# TinyCube13_FourLayer.net
KiCad netlist of a schematic drawn in EAGLE
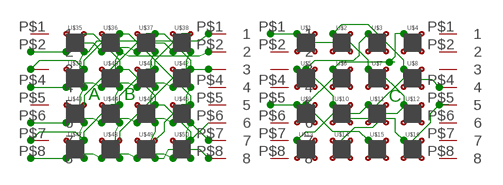
[diagram p0: schematic, sheet 1]

(export (version "E")
  (design (tool "Eeschema 10.0.6"))
  (components
    (comp (ref "JP1")
      (value "TINY_HEADER_DEV")
      (footprint "eagle-import:TINY_HEADER_PKG")
      (libsource (lib "eagle-import") (part "TINY_HEADER_DEV"))
    )
    (comp (ref "JP2")
      (value "TINY_HEADER_DEV")
      (footprint "eagle-import:TINY_HEADER_PKG")
      (libsource (lib "eagle-import") (part "TINY_HEADER_DEV"))
    )
    (comp (ref "U$1")
      (value "PILLAR")
      (footprint "eagle-import:10MIL")
      (libsource (lib "eagle-import") (part "PILLAR"))
    )
    (comp (ref "U$2")
      (value "PILLAR")
      (footprint "eagle-import:10MIL")
      (libsource (lib "eagle-import") (part "PILLAR"))
    )
    (comp (ref "U$3")
      (value "PILLAR")
      (footprint "eagle-import:10MIL")
      (libsource (lib "eagle-import") (part "PILLAR"))
    )
    (comp (ref "U$4")
      (value "PILLAR")
      (footprint "eagle-import:10MIL")
      (libsource (lib "eagle-import") (part "PILLAR"))
    )
    (comp (ref "U$5")
      (value "PILLAR")
      (footprint "eagle-import:10MIL")
      (libsource (lib "eagle-import") (part "PILLAR"))
    )
    (comp (ref "U$6")
      (value "PILLAR")
      (footprint "eagle-import:10MIL")
      (libsource (lib "eagle-import") (part "PILLAR"))
    )
    (comp (ref "U$7")
      (value "PILLAR")
      (footprint "eagle-import:10MIL")
      (libsource (lib "eagle-import") (part "PILLAR"))
    )
    (comp (ref "U$8")
      (value "PILLAR")
      (footprint "eagle-import:10MIL")
      (libsource (lib "eagle-import") (part "PILLAR"))
    )
    (comp (ref "U$9")
      (value "PILLAR")
      (footprint "eagle-import:10MIL")
      (libsource (lib "eagle-import") (part "PILLAR"))
    )
    (comp (ref "U$10")
      (value "PILLAR")
      (footprint "eagle-import:10MIL")
      (libsource (lib "eagle-import") (part "PILLAR"))
    )
    (comp (ref "U$11")
      (value "PILLAR")
      (footprint "eagle-import:10MIL")
      (libsource (lib "eagle-import") (part "PILLAR"))
    )
    (comp (ref "U$12")
      (value "PILLAR")
      (footprint "eagle-import:10MIL")
      (libsource (lib "eagle-import") (part "PILLAR"))
    )
    (comp (ref "U$13")
      (value "PILLAR")
      (footprint "eagle-import:10MIL")
      (libsource (lib "eagle-import") (part "PILLAR"))
    )
    (comp (ref "U$14")
      (value "PILLAR")
      (footprint "eagle-import:10MIL")
      (libsource (lib "eagle-import") (part "PILLAR"))
    )
    (comp (ref "U$15")
      (value "PILLAR")
      (footprint "eagle-import:10MIL")
      (libsource (lib "eagle-import") (part "PILLAR"))
    )
    (comp (ref "U$16")
      (value "PILLAR")
      (footprint "eagle-import:10MIL")
      (libsource (lib "eagle-import") (part "PILLAR"))
    )
    (comp (ref "U$35")
      (value "PILLAR")
      (footprint "eagle-import:10MIL")
      (libsource (lib "eagle-import") (part "PILLAR"))
    )
    (comp (ref "U$36")
      (value "PILLAR")
      (footprint "eagle-import:10MIL")
      (libsource (lib "eagle-import") (part "PILLAR"))
    )
    (comp (ref "U$37")
      (value "PILLAR")
      (footprint "eagle-import:10MIL")
      (libsource (lib "eagle-import") (part "PILLAR"))
    )
    (comp (ref "U$38")
      (value "PILLAR")
      (footprint "eagle-import:10MIL")
      (libsource (lib "eagle-import") (part "PILLAR"))
    )
    (comp (ref "U$39")
      (value "PILLAR")
      (footprint "eagle-import:10MIL")
      (libsource (lib "eagle-import") (part "PILLAR"))
    )
    (comp (ref "U$40")
      (value "PILLAR")
      (footprint "eagle-import:10MIL")
      (libsource (lib "eagle-import") (part "PILLAR"))
    )
    (comp (ref "U$41")
      (value "PILLAR")
      (footprint "eagle-import:10MIL")
      (libsource (lib "eagle-import") (part "PILLAR"))
    )
    (comp (ref "U$42")
      (value "PILLAR")
      (footprint "eagle-import:10MIL")
      (libsource (lib "eagle-import") (part "PILLAR"))
    )
    (comp (ref "U$43")
      (value "PILLAR")
      (footprint "eagle-import:10MIL")
      (libsource (lib "eagle-import") (part "PILLAR"))
    )
    (comp (ref "U$44")
      (value "PILLAR")
      (footprint "eagle-import:10MIL")
      (libsource (lib "eagle-import") (part "PILLAR"))
    )
    (comp (ref "U$45")
      (value "PILLAR")
      (footprint "eagle-import:10MIL")
      (libsource (lib "eagle-import") (part "PILLAR"))
    )
    (comp (ref "U$46")
      (value "PILLAR")
      (footprint "eagle-import:10MIL")
      (libsource (lib "eagle-import") (part "PILLAR"))
    )
    (comp (ref "U$47")
      (value "PILLAR")
      (footprint "eagle-import:10MIL")
      (libsource (lib "eagle-import") (part "PILLAR"))
    )
    (comp (ref "U$48")
      (value "PILLAR")
      (footprint "eagle-import:10MIL")
      (libsource (lib "eagle-import") (part "PILLAR"))
    )
    (comp (ref "U$49")
      (value "PILLAR")
      (footprint "eagle-import:10MIL")
      (libsource (lib "eagle-import") (part "PILLAR"))
    )
    (comp (ref "U$50")
      (value "PILLAR")
      (footprint "eagle-import:10MIL")
      (libsource (lib "eagle-import") (part "PILLAR"))
    )
    (comp (ref "U$51")
      (value "TINY_HEADER_DEV")
      (footprint "eagle-import:TINY_HEADER_PKG")
      (libsource (lib "eagle-import") (part "TINY_HEADER_DEV"))
    )
    (comp (ref "U$52")
      (value "TINY_HEADER_DEV")
      (footprint "eagle-import:TINY_HEADER_PKG")
      (libsource (lib "eagle-import") (part "TINY_HEADER_DEV"))
    )
  )
  (nets
    (net (code "1") (name "Net-(JP1-1)") (class "Default")
      (node (ref "JP1") (pin "P$1") (pinfunction "1_P$1") (pintype "input"))
      (node (ref "U$1") (pin "R") (pinfunction "B_R") (pintype "bidirectional"))
      (node (ref "U$12") (pin "R") (pinfunction "B_R") (pintype "bidirectional"))
      (node (ref "U$14") (pin "R") (pinfunction "B_R") (pintype "bidirectional"))
      (node (ref "U$7") (pin "R") (pinfunction "B_R") (pintype "bidirectional"))
    )
    (net (code "2") (name "Net-(JP1-5)") (class "Default")
      (node (ref "JP1") (pin "P$5") (pinfunction "5_P$5") (pintype "bidirectional"))
      (node (ref "U$15") (pin "R") (pinfunction "B_R") (pintype "bidirectional"))
      (node (ref "U$4") (pin "R") (pinfunction "B_R") (pintype "bidirectional"))
      (node (ref "U$6") (pin "R") (pinfunction "B_R") (pintype "bidirectional"))
      (node (ref "U$9") (pin "R") (pinfunction "B_R") (pintype "bidirectional"))
    )
    (net (code "3") (name "Net-(JP2-4)") (class "Default")
      (node (ref "JP2") (pin "P$4") (pinfunction "4_P$4") (pintype "bidirectional"))
      (node (ref "U$11") (pin "R") (pinfunction "B_R") (pintype "bidirectional"))
      (node (ref "U$13") (pin "R") (pinfunction "B_R") (pintype "bidirectional"))
      (node (ref "U$2") (pin "R") (pinfunction "B_R") (pintype "bidirectional"))
      (node (ref "U$8") (pin "R") (pinfunction "B_R") (pintype "bidirectional"))
    )
    (net (code "4") (name "Net-(JP2-5)") (class "Default")
      (node (ref "JP2") (pin "P$5") (pinfunction "5_P$5") (pintype "bidirectional"))
      (node (ref "U$10") (pin "R") (pinfunction "B_R") (pintype "bidirectional"))
      (node (ref "U$16") (pin "R") (pinfunction "B_R") (pintype "bidirectional"))
      (node (ref "U$3") (pin "R") (pinfunction "B_R") (pintype "bidirectional"))
      (node (ref "U$5") (pin "R") (pinfunction "B_R") (pintype "bidirectional"))
    )
    (net (code "5") (name "Net-(U$35-A)") (class "Default")
      (node (ref "U$35") (pin "G") (pinfunction "A_G") (pintype "bidirectional"))
      (node (ref "U$36") (pin "G") (pinfunction "A_G") (pintype "bidirectional"))
      (node (ref "U$37") (pin "G") (pinfunction "A_G") (pintype "bidirectional"))
      (node (ref "U$38") (pin "G") (pinfunction "A_G") (pintype "bidirectional"))
      (node (ref "U$51") (pin "P$2") (pinfunction "2_P$2") (pintype "bidirectional"))
    )
    (net (code "6") (name "Net-(U$35-G)") (class "Default")
      (node (ref "U$35") (pin "+") (pinfunction "G_+") (pintype "bidirectional"))
      (node (ref "U$40") (pin "+") (pinfunction "G_+") (pintype "bidirectional"))
      (node (ref "U$45") (pin "+") (pinfunction "G_+") (pintype "bidirectional"))
      (node (ref "U$50") (pin "+") (pinfunction "G_+") (pintype "bidirectional"))
      (node (ref "U$52") (pin "P$6") (pinfunction "6_P$6") (pintype "bidirectional"))
    )
    (net (code "7") (name "Net-(U$35-R)") (class "Default")
      (node (ref "U$35") (pin "B") (pinfunction "R_B") (pintype "bidirectional"))
      (node (ref "U$39") (pin "B") (pinfunction "R_B") (pintype "bidirectional"))
      (node (ref "U$43") (pin "B") (pinfunction "R_B") (pintype "bidirectional"))
      (node (ref "U$47") (pin "B") (pinfunction "R_B") (pintype "bidirectional"))
      (node (ref "U$52") (pin "P$1") (pinfunction "1_P$1") (pintype "input"))
    )
    (net (code "8") (name "Net-(U$36-G)") (class "Default")
      (node (ref "U$36") (pin "+") (pinfunction "G_+") (pintype "bidirectional"))
      (node (ref "U$39") (pin "+") (pinfunction "G_+") (pintype "bidirectional"))
      (node (ref "U$46") (pin "+") (pinfunction "G_+") (pintype "bidirectional"))
      (node (ref "U$49") (pin "+") (pinfunction "G_+") (pintype "bidirectional"))
      (node (ref "U$51") (pin "P$3") (pinfunction "3_P$3") (pintype "bidirectional"))
    )
    (net (code "9") (name "Net-(U$36-R)") (class "Default")
      (node (ref "U$36") (pin "B") (pinfunction "R_B") (pintype "bidirectional"))
      (node (ref "U$40") (pin "B") (pinfunction "R_B") (pintype "bidirectional"))
      (node (ref "U$44") (pin "B") (pinfunction "R_B") (pintype "bidirectional"))
      (node (ref "U$48") (pin "B") (pinfunction "R_B") (pintype "bidirectional"))
      (node (ref "U$52") (pin "P$2") (pinfunction "2_P$2") (pintype "bidirectional"))
    )
    (net (code "10") (name "Net-(U$37-G)") (class "Default")
      (node (ref "U$37") (pin "+") (pinfunction "G_+") (pintype "bidirectional"))
      (node (ref "U$42") (pin "+") (pinfunction "G_+") (pintype "bidirectional"))
      (node (ref "U$43") (pin "+") (pinfunction "G_+") (pintype "bidirectional"))
      (node (ref "U$48") (pin "+") (pinfunction "G_+") (pintype "bidirectional"))
      (node (ref "U$52") (pin "P$3") (pinfunction "3_P$3") (pintype "bidirectional"))
    )
    (net (code "11") (name "Net-(U$37-R)") (class "Default")
      (node (ref "U$37") (pin "B") (pinfunction "R_B") (pintype "bidirectional"))
      (node (ref "U$41") (pin "B") (pinfunction "R_B") (pintype "bidirectional"))
      (node (ref "U$45") (pin "B") (pinfunction "R_B") (pintype "bidirectional"))
      (node (ref "U$49") (pin "B") (pinfunction "R_B") (pintype "bidirectional"))
      (node (ref "U$52") (pin "P$8") (pinfunction "8_P$8") (pintype "bidirectional"))
    )
    (net (code "12") (name "Net-(U$38-G)") (class "Default")
      (node (ref "U$38") (pin "+") (pinfunction "G_+") (pintype "bidirectional"))
      (node (ref "U$41") (pin "+") (pinfunction "G_+") (pintype "bidirectional"))
      (node (ref "U$44") (pin "+") (pinfunction "G_+") (pintype "bidirectional"))
      (node (ref "U$47") (pin "+") (pinfunction "G_+") (pintype "bidirectional"))
      (node (ref "U$51") (pin "P$7") (pinfunction "7_P$7") (pintype "bidirectional"))
    )
    (net (code "13") (name "Net-(U$38-R)") (class "Default")
      (node (ref "U$38") (pin "B") (pinfunction "R_B") (pintype "bidirectional"))
      (node (ref "U$42") (pin "B") (pinfunction "R_B") (pintype "bidirectional"))
      (node (ref "U$46") (pin "B") (pinfunction "R_B") (pintype "bidirectional"))
      (node (ref "U$50") (pin "B") (pinfunction "R_B") (pintype "bidirectional"))
      (node (ref "U$52") (pin "P$7") (pinfunction "7_P$7") (pintype "bidirectional"))
    )
    (net (code "14") (name "Net-(U$39-A)") (class "Default")
      (node (ref "U$39") (pin "G") (pinfunction "A_G") (pintype "bidirectional"))
      (node (ref "U$40") (pin "G") (pinfunction "A_G") (pintype "bidirectional"))
      (node (ref "U$41") (pin "G") (pinfunction "A_G") (pintype "bidirectional"))
      (node (ref "U$42") (pin "G") (pinfunction "A_G") (pintype "bidirectional"))
      (node (ref "U$51") (pin "P$4") (pinfunction "4_P$4") (pintype "bidirectional"))
    )
    (net (code "15") (name "Net-(U$43-A)") (class "Default")
      (node (ref "U$43") (pin "G") (pinfunction "A_G") (pintype "bidirectional"))
      (node (ref "U$44") (pin "G") (pinfunction "A_G") (pintype "bidirectional"))
      (node (ref "U$45") (pin "G") (pinfunction "A_G") (pintype "bidirectional"))
      (node (ref "U$46") (pin "G") (pinfunction "A_G") (pintype "bidirectional"))
      (node (ref "U$51") (pin "P$6") (pinfunction "6_P$6") (pintype "bidirectional"))
    )
    (net (code "16") (name "Net-(U$47-A)") (class "Default")
      (node (ref "U$47") (pin "G") (pinfunction "A_G") (pintype "bidirectional"))
      (node (ref "U$48") (pin "G") (pinfunction "A_G") (pintype "bidirectional"))
      (node (ref "U$49") (pin "G") (pinfunction "A_G") (pintype "bidirectional"))
      (node (ref "U$50") (pin "G") (pinfunction "A_G") (pintype "bidirectional"))
      (node (ref "U$51") (pin "P$8") (pinfunction "8_P$8") (pintype "bidirectional"))
    )
    (net (code "17") (name "unconnected-(JP1-2-PadP$2)") (class "Default")
      (node (ref "JP1") (pin "P$2") (pinfunction "2_P$2") (pintype "bidirectional"))
    )
    (net (code "18") (name "unconnected-(JP1-3-PadP$3)") (class "Default")
      (node (ref "JP1") (pin "P$3") (pinfunction "3_P$3") (pintype "bidirectional"))
    )
    (net (code "19") (name "unconnected-(JP1-4-PadP$4)") (class "Default")
      (node (ref "JP1") (pin "P$4") (pinfunction "4_P$4") (pintype "bidirectional"))
    )
    (net (code "20") (name "unconnected-(JP1-6-PadP$6)") (class "Default")
      (node (ref "JP1") (pin "P$6") (pinfunction "6_P$6") (pintype "bidirectional"))
    )
    (net (code "21") (name "unconnected-(JP1-7-PadP$7)") (class "Default")
      (node (ref "JP1") (pin "P$7") (pinfunction "7_P$7") (pintype "bidirectional"))
    )
    (net (code "22") (name "unconnected-(JP1-8-PadP$8)") (class "Default")
      (node (ref "JP1") (pin "P$8") (pinfunction "8_P$8") (pintype "bidirectional"))
    )
    (net (code "23") (name "unconnected-(JP2-1-PadP$1)") (class "Default")
      (node (ref "JP2") (pin "P$1") (pinfunction "1_P$1") (pintype "input"))
    )
    (net (code "24") (name "unconnected-(JP2-2-PadP$2)") (class "Default")
      (node (ref "JP2") (pin "P$2") (pinfunction "2_P$2") (pintype "bidirectional"))
    )
    (net (code "25") (name "unconnected-(JP2-3-PadP$3)") (class "Default")
      (node (ref "JP2") (pin "P$3") (pinfunction "3_P$3") (pintype "bidirectional"))
    )
    (net (code "26") (name "unconnected-(JP2-6-PadP$6)") (class "Default")
      (node (ref "JP2") (pin "P$6") (pinfunction "6_P$6") (pintype "bidirectional"))
    )
    (net (code "27") (name "unconnected-(JP2-7-PadP$7)") (class "Default")
      (node (ref "JP2") (pin "P$7") (pinfunction "7_P$7") (pintype "bidirectional"))
    )
    (net (code "28") (name "unconnected-(JP2-8-PadP$8)") (class "Default")
      (node (ref "JP2") (pin "P$8") (pinfunction "8_P$8") (pintype "bidirectional"))
    )
    (net (code "29") (name "unconnected-(U$1-A-PadG)") (class "Default")
      (node (ref "U$1") (pin "G") (pinfunction "A_G") (pintype "bidirectional"))
    )
    (net (code "30") (name "unconnected-(U$1-G-Pad+)") (class "Default")
      (node (ref "U$1") (pin "+") (pinfunction "G_+") (pintype "bidirectional"))
    )
    (net (code "31") (name "unconnected-(U$1-R-PadB)") (class "Default")
      (node (ref "U$1") (pin "B") (pinfunction "R_B") (pintype "bidirectional"))
    )
    (net (code "32") (name "unconnected-(U$2-A-PadG)") (class "Default")
      (node (ref "U$2") (pin "G") (pinfunction "A_G") (pintype "bidirectional"))
    )
    (net (code "33") (name "unconnected-(U$2-G-Pad+)") (class "Default")
      (node (ref "U$2") (pin "+") (pinfunction "G_+") (pintype "bidirectional"))
    )
    (net (code "34") (name "unconnected-(U$2-R-PadB)") (class "Default")
      (node (ref "U$2") (pin "B") (pinfunction "R_B") (pintype "bidirectional"))
    )
    (net (code "35") (name "unconnected-(U$3-A-PadG)") (class "Default")
      (node (ref "U$3") (pin "G") (pinfunction "A_G") (pintype "bidirectional"))
    )
    (net (code "36") (name "unconnected-(U$3-G-Pad+)") (class "Default")
      (node (ref "U$3") (pin "+") (pinfunction "G_+") (pintype "bidirectional"))
    )
    (net (code "37") (name "unconnected-(U$3-R-PadB)") (class "Default")
      (node (ref "U$3") (pin "B") (pinfunction "R_B") (pintype "bidirectional"))
    )
    (net (code "38") (name "unconnected-(U$4-A-PadG)") (class "Default")
      (node (ref "U$4") (pin "G") (pinfunction "A_G") (pintype "bidirectional"))
    )
    (net (code "39") (name "unconnected-(U$4-G-Pad+)") (class "Default")
      (node (ref "U$4") (pin "+") (pinfunction "G_+") (pintype "bidirectional"))
    )
    (net (code "40") (name "unconnected-(U$4-R-PadB)") (class "Default")
      (node (ref "U$4") (pin "B") (pinfunction "R_B") (pintype "bidirectional"))
    )
    (net (code "41") (name "unconnected-(U$5-A-PadG)") (class "Default")
      (node (ref "U$5") (pin "G") (pinfunction "A_G") (pintype "bidirectional"))
    )
    (net (code "42") (name "unconnected-(U$5-G-Pad+)") (class "Default")
      (node (ref "U$5") (pin "+") (pinfunction "G_+") (pintype "bidirectional"))
    )
    (net (code "43") (name "unconnected-(U$5-R-PadB)") (class "Default")
      (node (ref "U$5") (pin "B") (pinfunction "R_B") (pintype "bidirectional"))
    )
    (net (code "44") (name "unconnected-(U$6-A-PadG)") (class "Default")
      (node (ref "U$6") (pin "G") (pinfunction "A_G") (pintype "bidirectional"))
    )
    (net (code "45") (name "unconnected-(U$6-G-Pad+)") (class "Default")
      (node (ref "U$6") (pin "+") (pinfunction "G_+") (pintype "bidirectional"))
    )
    (net (code "46") (name "unconnected-(U$6-R-PadB)") (class "Default")
      (node (ref "U$6") (pin "B") (pinfunction "R_B") (pintype "bidirectional"))
    )
    (net (code "47") (name "unconnected-(U$7-A-PadG)") (class "Default")
      (node (ref "U$7") (pin "G") (pinfunction "A_G") (pintype "bidirectional"))
    )
    (net (code "48") (name "unconnected-(U$7-G-Pad+)") (class "Default")
      (node (ref "U$7") (pin "+") (pinfunction "G_+") (pintype "bidirectional"))
    )
    (net (code "49") (name "unconnected-(U$7-R-PadB)") (class "Default")
      (node (ref "U$7") (pin "B") (pinfunction "R_B") (pintype "bidirectional"))
    )
    (net (code "50") (name "unconnected-(U$8-A-PadG)") (class "Default")
      (node (ref "U$8") (pin "G") (pinfunction "A_G") (pintype "bidirectional"))
    )
    (net (code "51") (name "unconnected-(U$8-G-Pad+)") (class "Default")
      (node (ref "U$8") (pin "+") (pinfunction "G_+") (pintype "bidirectional"))
    )
    (net (code "52") (name "unconnected-(U$8-R-PadB)") (class "Default")
      (node (ref "U$8") (pin "B") (pinfunction "R_B") (pintype "bidirectional"))
    )
    (net (code "53") (name "unconnected-(U$9-A-PadG)") (class "Default")
      (node (ref "U$9") (pin "G") (pinfunction "A_G") (pintype "bidirectional"))
    )
    (net (code "54") (name "unconnected-(U$9-G-Pad+)") (class "Default")
      (node (ref "U$9") (pin "+") (pinfunction "G_+") (pintype "bidirectional"))
    )
    (net (code "55") (name "unconnected-(U$9-R-PadB)") (class "Default")
      (node (ref "U$9") (pin "B") (pinfunction "R_B") (pintype "bidirectional"))
    )
    (net (code "56") (name "unconnected-(U$10-A-PadG)") (class "Default")
      (node (ref "U$10") (pin "G") (pinfunction "A_G") (pintype "bidirectional"))
    )
    (net (code "57") (name "unconnected-(U$10-G-Pad+)") (class "Default")
      (node (ref "U$10") (pin "+") (pinfunction "G_+") (pintype "bidirectional"))
    )
    (net (code "58") (name "unconnected-(U$10-R-PadB)") (class "Default")
      (node (ref "U$10") (pin "B") (pinfunction "R_B") (pintype "bidirectional"))
    )
    (net (code "59") (name "unconnected-(U$11-A-PadG)") (class "Default")
      (node (ref "U$11") (pin "G") (pinfunction "A_G") (pintype "bidirectional"))
    )
    (net (code "60") (name "unconnected-(U$11-G-Pad+)") (class "Default")
      (node (ref "U$11") (pin "+") (pinfunction "G_+") (pintype "bidirectional"))
    )
    (net (code "61") (name "unconnected-(U$11-R-PadB)") (class "Default")
      (node (ref "U$11") (pin "B") (pinfunction "R_B") (pintype "bidirectional"))
    )
    (net (code "62") (name "unconnected-(U$12-A-PadG)") (class "Default")
      (node (ref "U$12") (pin "G") (pinfunction "A_G") (pintype "bidirectional"))
    )
    (net (code "63") (name "unconnected-(U$12-G-Pad+)") (class "Default")
      (node (ref "U$12") (pin "+") (pinfunction "G_+") (pintype "bidirectional"))
    )
    (net (code "64") (name "unconnected-(U$12-R-PadB)") (class "Default")
      (node (ref "U$12") (pin "B") (pinfunction "R_B") (pintype "bidirectional"))
    )
    (net (code "65") (name "unconnected-(U$13-A-PadG)") (class "Default")
      (node (ref "U$13") (pin "G") (pinfunction "A_G") (pintype "bidirectional"))
    )
    (net (code "66") (name "unconnected-(U$13-G-Pad+)") (class "Default")
      (node (ref "U$13") (pin "+") (pinfunction "G_+") (pintype "bidirectional"))
    )
    (net (code "67") (name "unconnected-(U$13-R-PadB)") (class "Default")
      (node (ref "U$13") (pin "B") (pinfunction "R_B") (pintype "bidirectional"))
    )
    (net (code "68") (name "unconnected-(U$14-A-PadG)") (class "Default")
      (node (ref "U$14") (pin "G") (pinfunction "A_G") (pintype "bidirectional"))
    )
    (net (code "69") (name "unconnected-(U$14-G-Pad+)") (class "Default")
      (node (ref "U$14") (pin "+") (pinfunction "G_+") (pintype "bidirectional"))
    )
    (net (code "70") (name "unconnected-(U$14-R-PadB)") (class "Default")
      (node (ref "U$14") (pin "B") (pinfunction "R_B") (pintype "bidirectional"))
    )
    (net (code "71") (name "unconnected-(U$15-A-PadG)") (class "Default")
      (node (ref "U$15") (pin "G") (pinfunction "A_G") (pintype "bidirectional"))
    )
    (net (code "72") (name "unconnected-(U$15-G-Pad+)") (class "Default")
      (node (ref "U$15") (pin "+") (pinfunction "G_+") (pintype "bidirectional"))
    )
    (net (code "73") (name "unconnected-(U$15-R-PadB)") (class "Default")
      (node (ref "U$15") (pin "B") (pinfunction "R_B") (pintype "bidirectional"))
    )
    (net (code "74") (name "unconnected-(U$16-A-PadG)") (class "Default")
      (node (ref "U$16") (pin "G") (pinfunction "A_G") (pintype "bidirectional"))
    )
    (net (code "75") (name "unconnected-(U$16-G-Pad+)") (class "Default")
      (node (ref "U$16") (pin "+") (pinfunction "G_+") (pintype "bidirectional"))
    )
    (net (code "76") (name "unconnected-(U$16-R-PadB)") (class "Default")
      (node (ref "U$16") (pin "B") (pinfunction "R_B") (pintype "bidirectional"))
    )
    (net (code "77") (name "unconnected-(U$35-B-PadR)") (class "Default")
      (node (ref "U$35") (pin "R") (pinfunction "B_R") (pintype "bidirectional"))
    )
    (net (code "78") (name "unconnected-(U$36-B-PadR)") (class "Default")
      (node (ref "U$36") (pin "R") (pinfunction "B_R") (pintype "bidirectional"))
    )
    (net (code "79") (name "unconnected-(U$37-B-PadR)") (class "Default")
      (node (ref "U$37") (pin "R") (pinfunction "B_R") (pintype "bidirectional"))
    )
    (net (code "80") (name "unconnected-(U$38-B-PadR)") (class "Default")
      (node (ref "U$38") (pin "R") (pinfunction "B_R") (pintype "bidirectional"))
    )
    (net (code "81") (name "unconnected-(U$39-B-PadR)") (class "Default")
      (node (ref "U$39") (pin "R") (pinfunction "B_R") (pintype "bidirectional"))
    )
    (net (code "82") (name "unconnected-(U$40-B-PadR)") (class "Default")
      (node (ref "U$40") (pin "R") (pinfunction "B_R") (pintype "bidirectional"))
    )
    (net (code "83") (name "unconnected-(U$41-B-PadR)") (class "Default")
      (node (ref "U$41") (pin "R") (pinfunction "B_R") (pintype "bidirectional"))
    )
    (net (code "84") (name "unconnected-(U$42-B-PadR)") (class "Default")
      (node (ref "U$42") (pin "R") (pinfunction "B_R") (pintype "bidirectional"))
    )
    (net (code "85") (name "unconnected-(U$43-B-PadR)") (class "Default")
      (node (ref "U$43") (pin "R") (pinfunction "B_R") (pintype "bidirectional"))
    )
    (net (code "86") (name "unconnected-(U$44-B-PadR)") (class "Default")
      (node (ref "U$44") (pin "R") (pinfunction "B_R") (pintype "bidirectional"))
    )
    (net (code "87") (name "unconnected-(U$45-B-PadR)") (class "Default")
      (node (ref "U$45") (pin "R") (pinfunction "B_R") (pintype "bidirectional"))
    )
    (net (code "88") (name "unconnected-(U$46-B-PadR)") (class "Default")
      (node (ref "U$46") (pin "R") (pinfunction "B_R") (pintype "bidirectional"))
    )
    (net (code "89") (name "unconnected-(U$47-B-PadR)") (class "Default")
      (node (ref "U$47") (pin "R") (pinfunction "B_R") (pintype "bidirectional"))
    )
    (net (code "90") (name "unconnected-(U$48-B-PadR)") (class "Default")
      (node (ref "U$48") (pin "R") (pinfunction "B_R") (pintype "bidirectional"))
    )
    (net (code "91") (name "unconnected-(U$49-B-PadR)") (class "Default")
      (node (ref "U$49") (pin "R") (pinfunction "B_R") (pintype "bidirectional"))
    )
    (net (code "92") (name "unconnected-(U$50-B-PadR)") (class "Default")
      (node (ref "U$50") (pin "R") (pinfunction "B_R") (pintype "bidirectional"))
    )
    (net (code "93") (name "unconnected-(U$51-1-PadP$1)") (class "Default")
      (node (ref "U$51") (pin "P$1") (pinfunction "1_P$1") (pintype "input"))
    )
    (net (code "94") (name "unconnected-(U$51-5-PadP$5)") (class "Default")
      (node (ref "U$51") (pin "P$5") (pinfunction "5_P$5") (pintype "bidirectional"))
    )
    (net (code "95") (name "unconnected-(U$52-4-PadP$4)") (class "Default")
      (node (ref "U$52") (pin "P$4") (pinfunction "4_P$4") (pintype "bidirectional"))
    )
    (net (code "96") (name "unconnected-(U$52-5-PadP$5)") (class "Default")
      (node (ref "U$52") (pin "P$5") (pinfunction "5_P$5") (pintype "bidirectional"))
    )
  )
)
